# UV_Arduino_PC_board.net
KiCad netlist of a schematic drawn in EAGLE
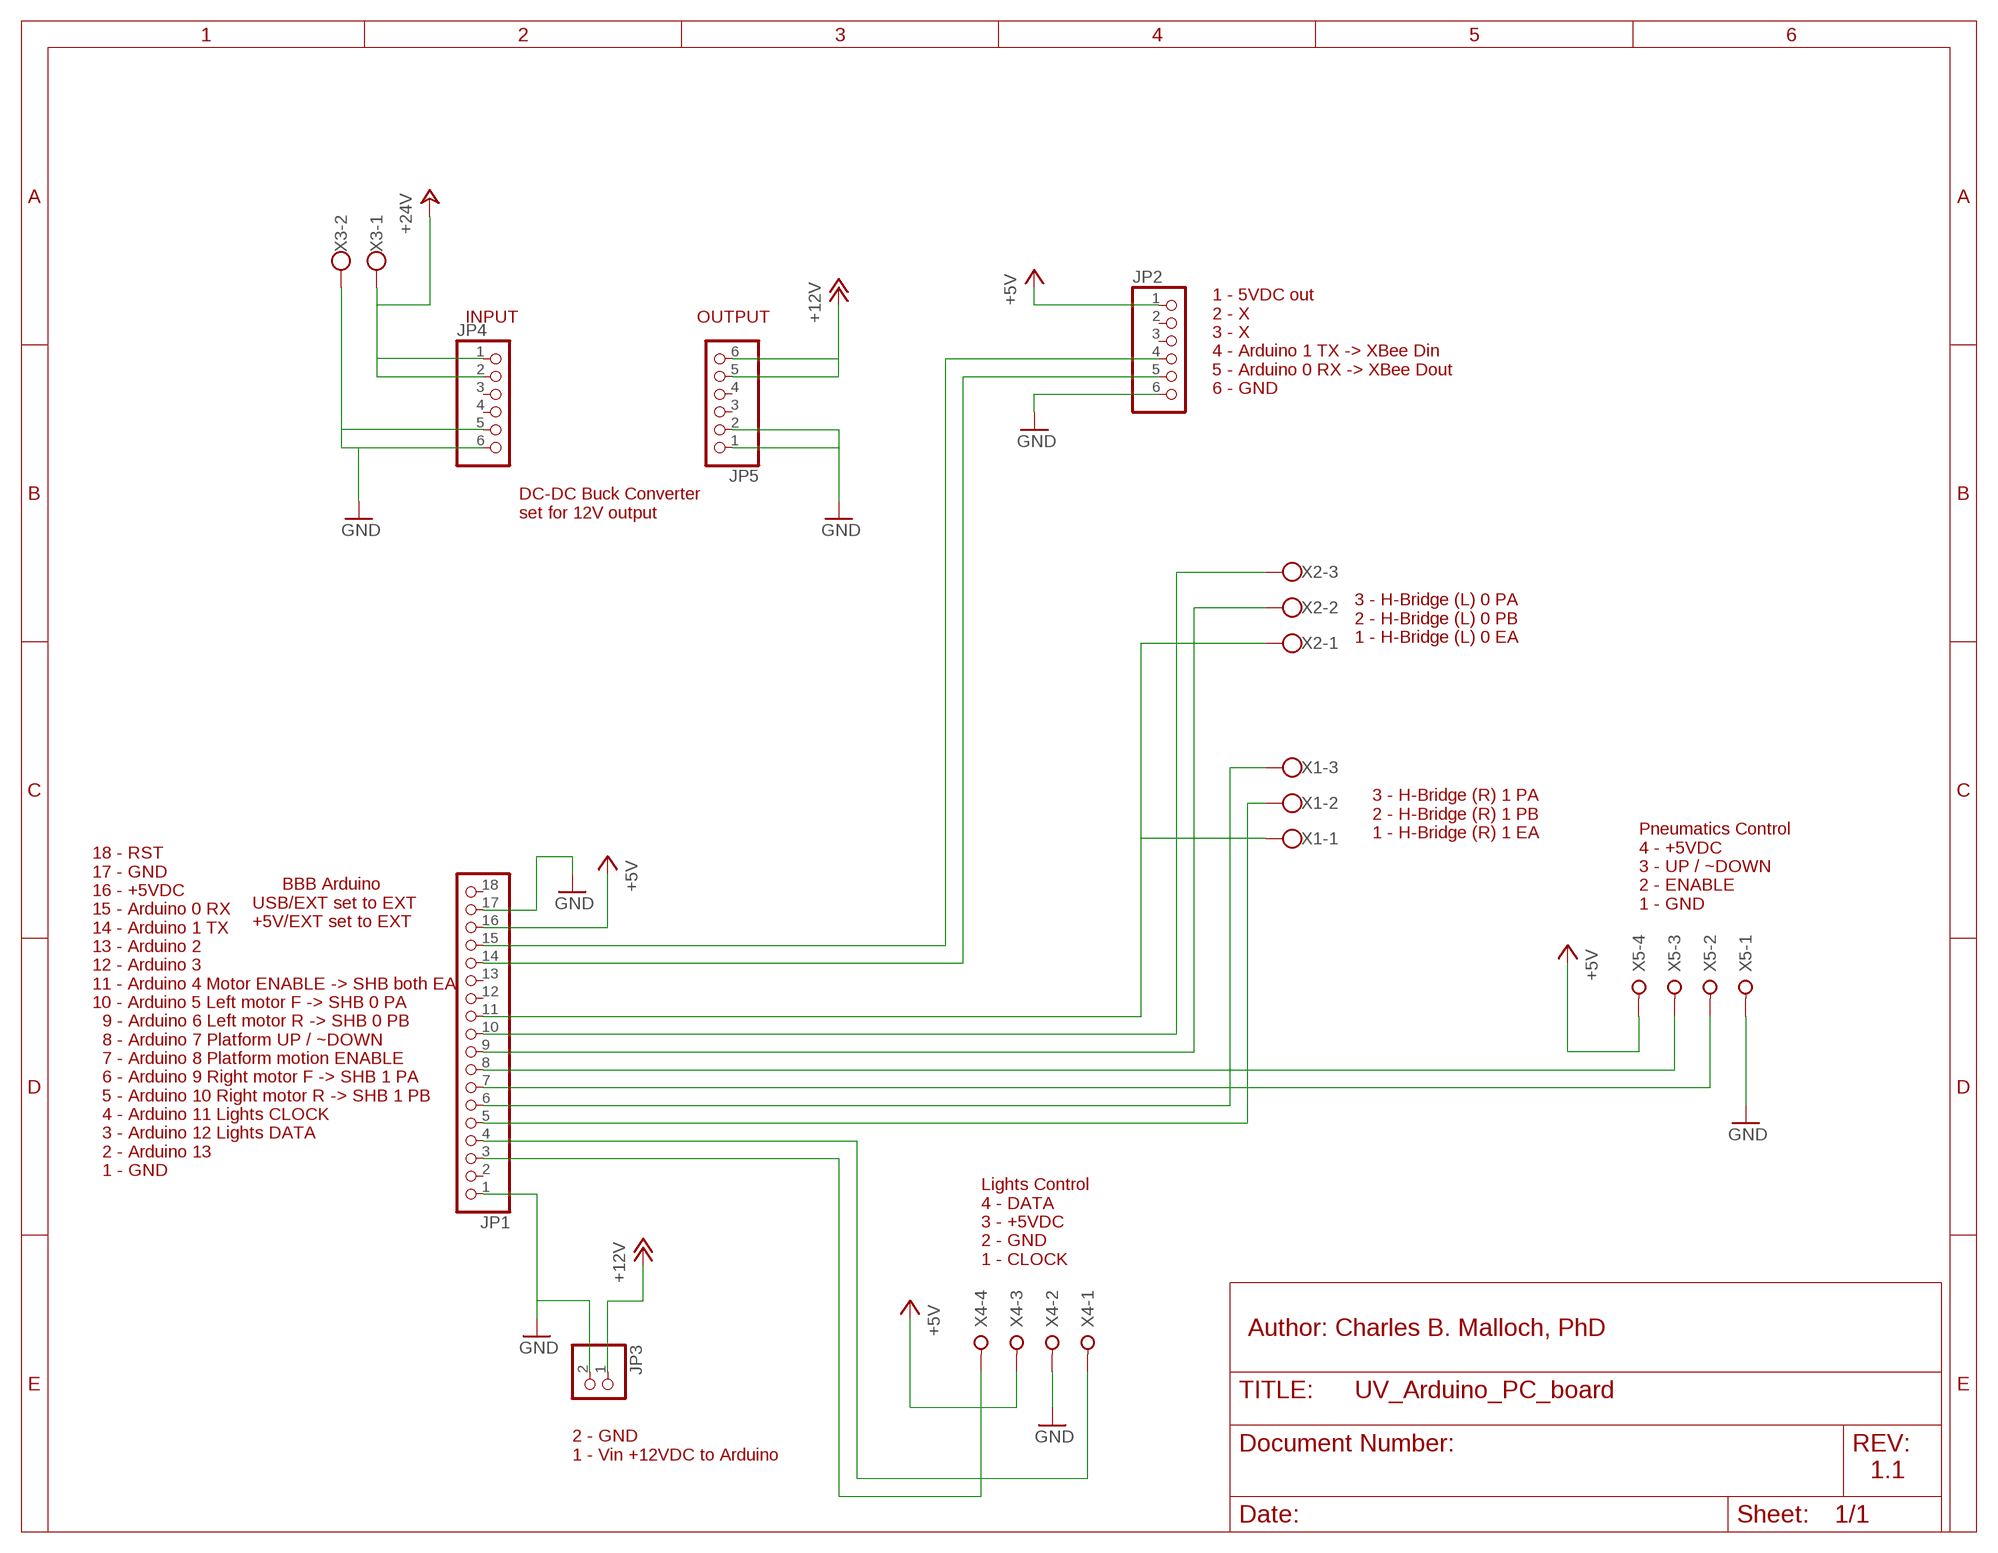
[diagram p0: schematic, sheet 1]

(export (version "E")
  (design (tool "Eeschema 10.0.6"))
  (components
    (comp (ref "JP1")
      (value "PINHD-1X18")
      (footprint "eagle-import:1X18")
      (libsource (lib "eagle-import") (part "PINHD-1X18"))
    )
    (comp (ref "JP2")
      (value "PINHD-1X6")
      (footprint "eagle-import:1X06")
      (libsource (lib "eagle-import") (part "PINHD-1X6"))
    )
    (comp (ref "JP3")
      (value "PINHD-1X2")
      (footprint "eagle-import:1X02")
      (libsource (lib "eagle-import") (part "PINHD-1X2"))
    )
    (comp (ref "JP4")
      (value "PINHD-1X6")
      (footprint "eagle-import:1X06")
      (libsource (lib "eagle-import") (part "PINHD-1X6"))
    )
    (comp (ref "JP5")
      (value "PINHD-1X6")
      (footprint "eagle-import:1X06")
      (libsource (lib "eagle-import") (part "PINHD-1X6"))
    )
    (comp (ref "X1")
      (value "W237-103")
      (footprint "eagle-import:W237-103")
      (fields (field (name "MPN") "237-103"))
      (libsource (lib "eagle-import") (part "W237-103"))
    )
    (comp (ref "X2")
      (value "W237-103")
      (footprint "eagle-import:W237-103")
      (fields (field (name "MPN") "237-103"))
      (libsource (lib "eagle-import") (part "W237-103"))
    )
    (comp (ref "X3")
      (value "W237-102")
      (footprint "eagle-import:W237-102")
      (fields (field (name "MPN") "237-102"))
      (libsource (lib "eagle-import") (part "W237-102"))
    )
    (comp (ref "X4")
      (value "W237-04P")
      (footprint "eagle-import:W237-4P")
      (libsource (lib "eagle-import") (part "W237-04P"))
    )
    (comp (ref "X5")
      (value "W237-04P")
      (footprint "eagle-import:W237-4P")
      (libsource (lib "eagle-import") (part "W237-04P"))
    )
  )
  (nets
    (net (code "1") (name "+5V") (class "Default")
      (node (ref "JP1") (pin "16") (pinfunction "16_16") (pintype "passive"))
      (node (ref "JP2") (pin "1") (pinfunction "1_1") (pintype "passive"))
      (node (ref "X4") (pin "3") (pinfunction "KL_3") (pintype "passive"))
      (node (ref "X5") (pin "4") (pinfunction "KL_4") (pintype "passive"))
    )
    (net (code "2") (name "+12V") (class "Default")
      (node (ref "JP3") (pin "1") (pinfunction "1_1") (pintype "passive"))
      (node (ref "JP5") (pin "5") (pinfunction "5_5") (pintype "passive"))
      (node (ref "JP5") (pin "6") (pinfunction "6_6") (pintype "passive"))
    )
    (net (code "4") (name "GND") (class "Default")
      (node (ref "JP1") (pin "1") (pinfunction "1_1") (pintype "passive"))
      (node (ref "JP1") (pin "17") (pinfunction "17_17") (pintype "passive"))
      (node (ref "JP2") (pin "6") (pinfunction "6_6") (pintype "passive"))
      (node (ref "JP3") (pin "2") (pinfunction "2_2") (pintype "passive"))
      (node (ref "JP4") (pin "5") (pinfunction "5_5") (pintype "passive"))
      (node (ref "JP4") (pin "6") (pinfunction "6_6") (pintype "passive"))
      (node (ref "JP5") (pin "1") (pinfunction "1_1") (pintype "passive"))
      (node (ref "JP5") (pin "2") (pinfunction "2_2") (pintype "passive"))
      (node (ref "X3") (pin "2") (pinfunction "KL_2") (pintype "passive"))
      (node (ref "X4") (pin "2") (pinfunction "KL_2") (pintype "passive"))
      (node (ref "X5") (pin "1") (pinfunction "KL_1") (pintype "passive"))
    )
    (net (code "5") (name "Net-(JP1-Pad14)") (class "Default")
      (node (ref "JP1") (pin "14") (pinfunction "14_14") (pintype "passive"))
      (node (ref "JP2") (pin "5") (pinfunction "5_5") (pintype "passive"))
    )
    (net (code "6") (name "Net-(JP1-Pad15)") (class "Default")
      (node (ref "JP1") (pin "15") (pinfunction "15_15") (pintype "passive"))
      (node (ref "JP2") (pin "4") (pinfunction "4_4") (pintype "passive"))
    )
    (net (code "7") (name "Net-(X1A-KL)") (class "Default")
      (node (ref "JP1") (pin "11") (pinfunction "11_11") (pintype "passive"))
      (node (ref "X1") (pin "1") (pinfunction "KL_1") (pintype "passive"))
      (node (ref "X2") (pin "1") (pinfunction "KL_1") (pintype "passive"))
    )
    (net (code "8") (name "Net-(X1B-KL)") (class "Default")
      (node (ref "JP1") (pin "5") (pinfunction "5_5") (pintype "passive"))
      (node (ref "X1") (pin "2") (pinfunction "KL_2") (pintype "passive"))
    )
    (net (code "9") (name "Net-(X1C-KL)") (class "Default")
      (node (ref "JP1") (pin "6") (pinfunction "6_6") (pintype "passive"))
      (node (ref "X1") (pin "3") (pinfunction "KL_3") (pintype "passive"))
    )
    (net (code "10") (name "Net-(X2B-KL)") (class "Default")
      (node (ref "JP1") (pin "9") (pinfunction "9_9") (pintype "passive"))
      (node (ref "X2") (pin "2") (pinfunction "KL_2") (pintype "passive"))
    )
    (net (code "11") (name "Net-(X2C-KL)") (class "Default")
      (node (ref "JP1") (pin "10") (pinfunction "10_10") (pintype "passive"))
      (node (ref "X2") (pin "3") (pinfunction "KL_3") (pintype "passive"))
    )
    (net (code "12") (name "Net-(X3A-KL)") (class "Default")
      (node (ref "JP4") (pin "1") (pinfunction "1_1") (pintype "passive"))
      (node (ref "JP4") (pin "2") (pinfunction "2_2") (pintype "passive"))
      (node (ref "X3") (pin "1") (pinfunction "KL_1") (pintype "passive"))
    )
    (net (code "13") (name "Net-(X4A-KL)") (class "Default")
      (node (ref "JP1") (pin "4") (pinfunction "4_4") (pintype "passive"))
      (node (ref "X4") (pin "1") (pinfunction "KL_1") (pintype "passive"))
    )
    (net (code "14") (name "Net-(X4D-KL)") (class "Default")
      (node (ref "JP1") (pin "3") (pinfunction "3_3") (pintype "passive"))
      (node (ref "X4") (pin "4") (pinfunction "KL_4") (pintype "passive"))
    )
    (net (code "15") (name "Net-(X5B-KL)") (class "Default")
      (node (ref "JP1") (pin "7") (pinfunction "7_7") (pintype "passive"))
      (node (ref "X5") (pin "2") (pinfunction "KL_2") (pintype "passive"))
    )
    (net (code "16") (name "Net-(X5C-KL)") (class "Default")
      (node (ref "JP1") (pin "8") (pinfunction "8_8") (pintype "passive"))
      (node (ref "X5") (pin "3") (pinfunction "KL_3") (pintype "passive"))
    )
    (net (code "17") (name "unconnected-(JP1-Pad2)") (class "Default")
      (node (ref "JP1") (pin "2") (pinfunction "2_2") (pintype "passive"))
    )
    (net (code "18") (name "unconnected-(JP1-Pad12)") (class "Default")
      (node (ref "JP1") (pin "12") (pinfunction "12_12") (pintype "passive"))
    )
    (net (code "19") (name "unconnected-(JP1-Pad13)") (class "Default")
      (node (ref "JP1") (pin "13") (pinfunction "13_13") (pintype "passive"))
    )
    (net (code "20") (name "unconnected-(JP1-Pad18)") (class "Default")
      (node (ref "JP1") (pin "18") (pinfunction "18_18") (pintype "passive"))
    )
    (net (code "21") (name "unconnected-(JP2-Pad2)") (class "Default")
      (node (ref "JP2") (pin "2") (pinfunction "2_2") (pintype "passive"))
    )
    (net (code "22") (name "unconnected-(JP2-Pad3)") (class "Default")
      (node (ref "JP2") (pin "3") (pinfunction "3_3") (pintype "passive"))
    )
    (net (code "23") (name "unconnected-(JP4-Pad3)") (class "Default")
      (node (ref "JP4") (pin "3") (pinfunction "3_3") (pintype "passive"))
    )
    (net (code "24") (name "unconnected-(JP4-Pad4)") (class "Default")
      (node (ref "JP4") (pin "4") (pinfunction "4_4") (pintype "passive"))
    )
    (net (code "25") (name "unconnected-(JP5-Pad3)") (class "Default")
      (node (ref "JP5") (pin "3") (pinfunction "3_3") (pintype "passive"))
    )
    (net (code "26") (name "unconnected-(JP5-Pad4)") (class "Default")
      (node (ref "JP5") (pin "4") (pinfunction "4_4") (pintype "passive"))
    )
  )
)
